# sch_station_de_charge.net
KiCad netlist of a schematic drawn in Altium Designer
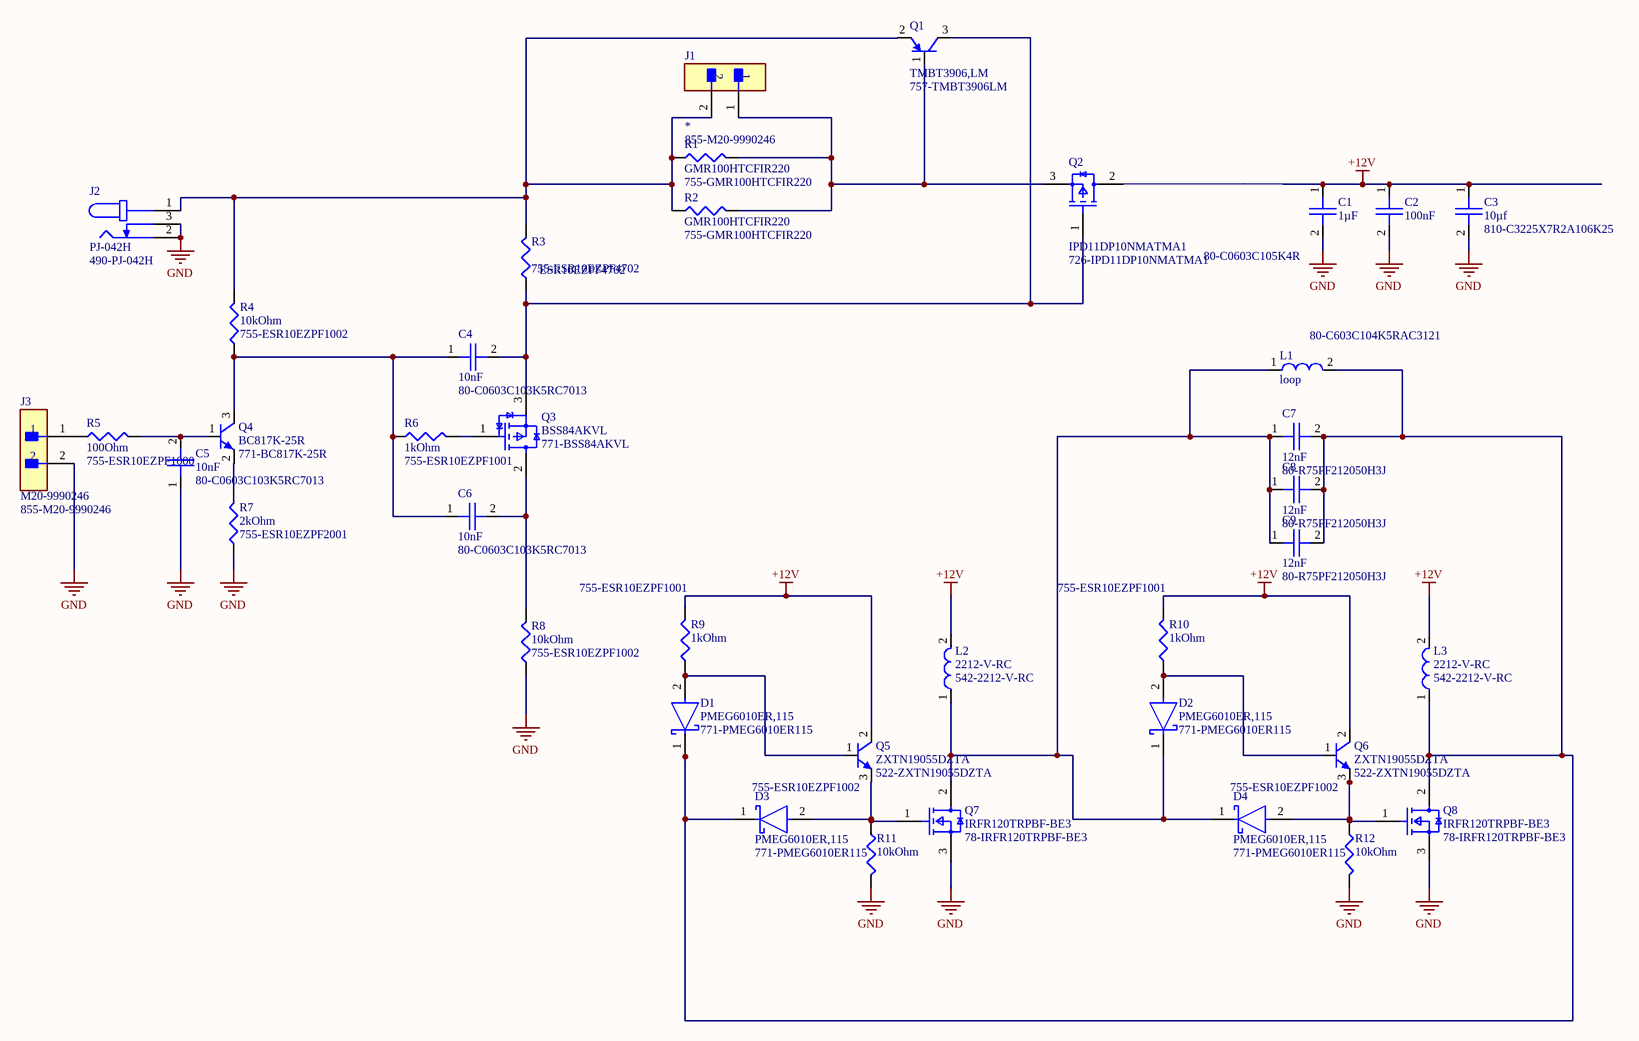
[diagram p0: sch_station_de_charge.SchDoc]

(export (version "E")
  (design (tool "Eeschema 10.0.6"))
  (components
    (comp (ref "C1")
      (value "1µF")
      (footprint "CAPC1608X90X35NL15T15")
      (description "Cap Ceramic 1uF 16V X7R 10% SMD 0603 125°C Paper T/R")
      (fields
        (field (name "MANUFACTURER") "KEMET")
        (field (name "MANUFACTURER PART NUMBER") "C0603C105K4RACTU")
        (field (name "SUPPLIER PART NUMBER 1") "80-C0603C105K4R")
      )
      (libsource (lib "station_de_charge_SchLib") (part "C0603C105K4RACTU"))
    )
    (comp (ref "C2")
      (value "100nF")
      (footprint "FP-C0603C104K5RAC3121-IPC_A")
      (description "Cap Ceramic 0.1uF 50V X7R 10% Pad SMD 0603 125°C T/R")
      (fields
        (field (name "MANUFACTURER") "KEMET")
        (field (name "MANUFACTURER PART NUMBER") "C0603C104K5RAC3121")
        (field (name "SUPPLIER PART NUMBER 1") "80-C603C104K5RAC3121")
      )
      (libsource (lib "lib_station_de_charge") (part "C0603C104K5RAC3121"))
    )
    (comp (ref "C3")
      (value "10µf")
      (footprint "CAPC3225X280N")
      (description "Multilayer Ceramic Chip Capacitors, Capacitance=10μF, LxWxT: 3.2x2.5x2.5mm")
      (fields
        (field (name "MANUFACTURER") "TDK")
        (field (name "MANUFACTURER PART NUMBER") "C3225X7R2A106K250AC")
        (field (name "SUPPLIER PART NUMBER 1") "810-C3225X7R2A106K25")
      )
      (libsource (lib "station_de_charge_SchLib") (part "C3225X7R2A106K250AC"))
    )
    (comp (ref "C4")
      (value "10nF")
      (footprint "FP-C0603C104K5RAC3121-IPC_A")
      (description "Cap Ceramic 0.01uF 50V X7R 10% Pad SMD 0603 125C T/R")
      (fields
        (field (name "MANUFACTURER") "KEMET")
        (field (name "MANUFACTURER PART NUMBER") "C0603C103K5RAC7013")
        (field (name "SUPPLIER PART NUMBER 1") "80-C0603C103K5RC7013")
      )
      (libsource (lib "station_de_charge_SchLib") (part "C0603C103K5RAC7013"))
    )
    (comp (ref "C5")
      (value "10nF")
      (footprint "FP-C0603C104K5RAC3121-IPC_A")
      (description "Cap Ceramic 0.01uF 50V X7R 10% Pad SMD 0603 125C T/R")
      (fields
        (field (name "MANUFACTURER") "KEMET")
        (field (name "MANUFACTURER PART NUMBER") "C0603C103K5RAC7013")
        (field (name "SUPPLIER PART NUMBER 1") "80-C0603C103K5RC7013")
      )
      (libsource (lib "station_de_charge_SchLib") (part "C0603C103K5RAC7013"))
    )
    (comp (ref "C6")
      (value "10nF")
      (footprint "FP-C0603C104K5RAC3121-IPC_A")
      (description "Cap Ceramic 0.01uF 50V X7R 10% Pad SMD 0603 125C T/R")
      (fields
        (field (name "MANUFACTURER") "KEMET")
        (field (name "MANUFACTURER PART NUMBER") "C0603C103K5RAC7013")
        (field (name "SUPPLIER PART NUMBER 1") "80-C0603C103K5RC7013")
      )
      (libsource (lib "station_de_charge_SchLib") (part "C0603C103K5RAC7013"))
    )
    (comp (ref "C7")
      (value "12nF")
      (footprint "R75PF212050H3J")
      (description "Cap Film 0.012uF 630V PP 5% Molded Solder Pin 10mm 125°C Bulk")
      (fields
        (field (name "MANUFACTURER") "KEMET")
        (field (name "MANUFACTURER PART NUMBER") "R75PF212050H3J")
        (field (name "SUPPLIER PART NUMBER 1") "80-R75PF212050H3J")
      )
      (libsource (lib "station_de_charge_SchLib") (part "R75PF212050H3J"))
    )
    (comp (ref "C8")
      (value "12nF")
      (footprint "R75PF212050H3J")
      (description "Cap Film 0.012uF 630V PP 5% Molded Solder Pin 10mm 125°C Bulk")
      (fields
        (field (name "MANUFACTURER") "KEMET")
        (field (name "MANUFACTURER PART NUMBER") "R75PF212050H3J")
        (field (name "SUPPLIER PART NUMBER 1") "80-R75PF212050H3J")
      )
      (libsource (lib "station_de_charge_SchLib") (part "R75PF212050H3J"))
    )
    (comp (ref "C9")
      (value "12nF")
      (footprint "R75PF212050H3J")
      (description "Cap Film 0.012uF 630V PP 5% Molded Solder Pin 10mm 125°C Bulk")
      (fields
        (field (name "MANUFACTURER") "KEMET")
        (field (name "MANUFACTURER PART NUMBER") "R75PF212050H3J")
        (field (name "SUPPLIER PART NUMBER 1") "80-R75PF212050H3J")
      )
      (libsource (lib "station_de_charge_SchLib") (part "R75PF212050H3J"))
    )
    (comp (ref "D1")
      (value "PMEG6010ER,115")
      (footprint "TVS_PTVS13VS1UR,115")
      (description "DIODE SCHOTTKY 60V 1A SOD123W")
      (fields
        (field (name "MANUFACTURER") "Nexperia")
        (field (name "SUPPLIER PART NUMBER 1") "771-PMEG6010ER115")
      )
      (libsource (lib "station_de_charge_SchLib") (part "PMEG6010ER,115"))
    )
    (comp (ref "D2")
      (value "PMEG6010ER,115")
      (footprint "TVS_PTVS13VS1UR,115")
      (description "DIODE SCHOTTKY 60V 1A SOD123W")
      (fields
        (field (name "MANUFACTURER") "Nexperia")
        (field (name "SUPPLIER PART NUMBER 1") "771-PMEG6010ER115")
      )
      (libsource (lib "station_de_charge_SchLib") (part "PMEG6010ER,115"))
    )
    (comp (ref "D3")
      (value "PMEG6010ER,115")
      (footprint "TVS_PTVS13VS1UR,115")
      (description "DIODE SCHOTTKY 60V 1A SOD123W")
      (fields
        (field (name "MANUFACTURER") "Nexperia")
        (field (name "SUPPLIER PART NUMBER 1") "771-PMEG6010ER115")
      )
      (libsource (lib "station_de_charge_SchLib") (part "PMEG6010ER,115"))
    )
    (comp (ref "D4")
      (value "PMEG6010ER,115")
      (footprint "TVS_PTVS13VS1UR,115")
      (description "DIODE SCHOTTKY 60V 1A SOD123W")
      (fields
        (field (name "MANUFACTURER") "Nexperia")
        (field (name "SUPPLIER PART NUMBER 1") "771-PMEG6010ER115")
      )
      (libsource (lib "station_de_charge_SchLib") (part "PMEG6010ER,115"))
    )
    (comp (ref "J1")
      (value "*")
      (footprint "FP-M20-9990246-MFG")
      (description "2.54mm (0.1\") Pitch SIL Vertical PC Tail Pin Header, 6.1mm mating pin height, tin, 2 contacts")
      (fields
        (field (name "MANUFACTURER") "Harwin")
        (field (name "MANUFACTURER PART NUMBER") "M20-9990246")
        (field (name "SUPPLIER PART NUMBER 1") "855-M20-9990246")
      )
      (libsource (lib "*") (part "M20-9990246"))
    )
    (comp (ref "J2")
      (value "PJ-042H")
      (footprint "CUI_PJ-042H")
      (description "1.65 x 5.15 mm, 5.0 A, Horizontal, Through Hole, Kinked Pins, Dc Power Jack Connector")
      (fields
        (field (name "MANUFACTURER") "CUI Devices")
        (field (name "SUPPLIER PART NUMBER 1") "490-PJ-042H")
      )
      (libsource (lib "station_de_charge_SchLib") (part "PJ-042H"))
    )
    (comp (ref "J3")
      (value "M20-9990246")
      (footprint "FP-M20-9990246-MFG")
      (description "2.54mm (0.1\") Pitch SIL Vertical PC Tail Pin Header, 6.1mm mating pin height, tin, 2 contacts")
      (fields
        (field (name "MANUFACTURER") "Harwin")
        (field (name "SUPPLIER PART NUMBER 1") "855-M20-9990246")
      )
      (libsource (lib "station_de_charge_SchLib") (part "M20-9990246"))
    )
    (comp (ref "L1")
      (value "loop")
      (footprint "loop")
      (libsource (lib "station_de_charge_SchLib") (part "loop"))
    )
    (comp (ref "L2")
      (value "2212-V-RC")
      (footprint "IND_HCTI-220-5.8")
      (description "Inductor High Current Toroid 100uH/64uH 15% 1KHz 4.4A 56mOhm DCR RDL")
      (fields
        (field (name "MANUFACTURER") "Bourns JW Miller")
        (field (name "TOLERANCE") "15%")
        (field (name "SUPPLIER PART NUMBER 1") "542-2212-V-RC")
      )
      (libsource (lib "station_de_charge_SchLib") (part "2212-V-RC"))
    )
    (comp (ref "L3")
      (value "2212-V-RC")
      (footprint "IND_HCTI-220-5.8")
      (description "Inductor High Current Toroid 100uH/64uH 15% 1KHz 4.4A 56mOhm DCR RDL")
      (fields
        (field (name "MANUFACTURER") "Bourns JW Miller")
        (field (name "TOLERANCE") "15%")
        (field (name "SUPPLIER PART NUMBER 1") "542-2212-V-RC")
      )
      (libsource (lib "station_de_charge_SchLib") (part "2212-V-RC"))
    )
    (comp (ref "Q1")
      (value "TMBT3906,LM")
      (footprint "FP-TMBT3906")
      (description "TRANSPNP50V0.15ASOT23-3")
      (fields
        (field (name "MANUFACTURER") "Toshiba")
        (field (name "SUPPLIER PART NUMBER 1") "757-TMBT3906LM")
      )
      (libsource (lib "station_de_charge_SchLib") (part "TMBT3906,LM"))
    )
    (comp (ref "Q2")
      (value "IPD11DP10NMATMA1")
      (footprint "FP-IPD11DP10NM")
      (description "Mosfet, P-ch, 100V, TO-252-3 Rohs Compliant: Yes")
      (fields
        (field (name "MANUFACTURER") "Infineon")
        (field (name "SUPPLIER PART NUMBER 1") "726-IPD11DP10NMATMA1")
      )
      (libsource (lib "station_de_charge_SchLib") (part "IPD11DP10NMATMA1"))
    )
    (comp (ref "Q3")
      (value "BSS84AKVL")
      (footprint "SOT95P230X110-3N")
      (description "BSS84AKV/SOT666/SOT6")
      (fields
        (field (name "MANUFACTURER") "Nexperia")
        (field (name "SUPPLIER PART NUMBER 1") "771-BSS84AKVL")
      )
      (libsource (lib "station_de_charge_SchLib") (part "BSS84AKVL"))
    )
    (comp (ref "Q4")
      (value "BC817K-25R")
      (footprint "SOT95P230X110-3N")
      (description "BC817K-25H/SOT23/TO-236AB")
      (fields
        (field (name "MANUFACTURER") "Nexperia")
        (field (name "SUPPLIER PART NUMBER 1") "771-BC817K-25R")
      )
      (libsource (lib "station_de_charge_SchLib") (part "BC817K-25R"))
    )
    (comp (ref "Q5")
      (value "ZXTN19055DZTA")
      (footprint "VREG_AP2204RA-3.3TRG1")
      (description "TRANS NPN 55V 6A SOT89")
      (fields
        (field (name "MANUFACTURER") "Diodes Zetex")
        (field (name "SUPPLIER PART NUMBER 1") "522-ZXTN19055DZTA")
      )
      (libsource (lib "lib_station_de_charge") (part "ZXTN19055DZTA"))
    )
    (comp (ref "Q6")
      (value "ZXTN19055DZTA")
      (footprint "VREG_AP2204RA-3.3TRG1")
      (description "TRANS NPN 55V 6A SOT89")
      (fields
        (field (name "MANUFACTURER") "Diodes Zetex")
        (field (name "SUPPLIER PART NUMBER 1") "522-ZXTN19055DZTA")
      )
      (libsource (lib "lib_station_de_charge") (part "ZXTN19055DZTA"))
    )
    (comp (ref "Q7")
      (value "IRFR120TRPBF-BE3")
      (footprint "FP-IRFR120TRPBF-BE3")
      (fields
        (field (name "MANUFACTURER") "Vishay Siliconix")
        (field (name "SUPPLIER PART NUMBER 1") "78-IRFR120TRPBF-BE3")
      )
      (libsource (lib "station_de_charge_SchLib") (part "IRFR120TRPBF-BE3"))
    )
    (comp (ref "Q8")
      (value "IRFR120TRPBF-BE3")
      (footprint "FP-IRFR120TRPBF-BE3")
      (fields
        (field (name "MANUFACTURER") "Vishay Siliconix")
        (field (name "SUPPLIER PART NUMBER 1") "78-IRFR120TRPBF-BE3")
      )
      (libsource (lib "station_de_charge_SchLib") (part "IRFR120TRPBF-BE3"))
    )
    (comp (ref "R1")
      (value "GMR100HTCFIR220")
      (footprint "RESC6432X55N")
      (description "Res Current Sense Metal Plate 2512 0.1 Ohm 1% 3W ±20ppm/°C Molded Emboss T/R")
      (fields
        (field (name "MANUFACTURER") "Rohm")
        (field (name "TOLERANCE") "1%")
        (field (name "SUPPLIER PART NUMBER 1") "755-GMR100HTCFIR220")
      )
      (libsource (lib "station_de_charge_SchLib") (part "GMR100HTCFIR220"))
    )
    (comp (ref "R2")
      (value "GMR100HTCFIR220")
      (footprint "RESC6432X55N")
      (description "Res Current Sense Metal Plate 2512 0.1 Ohm 1% 3W ±20ppm/°C Molded Emboss T/R")
      (fields
        (field (name "MANUFACTURER") "Rohm")
        (field (name "TOLERANCE") "1%")
        (field (name "SUPPLIER PART NUMBER 1") "755-GMR100HTCFIR220")
      )
      (libsource (lib "station_de_charge_SchLib") (part "GMR100HTCFIR220"))
    )
    (comp (ref "R3")
      (value "ESR10EZPF4702")
      (footprint "FP-ESR10-IPC_A")
      (description "Res Thick Film 0805 47K Ohm 1% 0.4W ±100ppm/C Pad SMD Automotive T/R")
      (fields
        (field (name "MANUFACTURER") "Rohm")
        (field (name "TOLERANCE") "1%")
        (field (name "SUPPLIER PART NUMBER 1") "755-ESR10EZPF4702")
      )
      (libsource (lib "station_de_charge_SchLib") (part "ESR10EZPF4702"))
    )
    (comp (ref "R4")
      (value "10kOhm")
      (footprint "FP-ESR10-IPC_A")
      (description "Res Thick Film 0805 10K Ohm 1% 0.4W ±100ppm/C Pad SMD Automotive T/R")
      (fields
        (field (name "MANUFACTURER") "Rohm")
        (field (name "MANUFACTURER PART NUMBER") "ESR10EZPF1002")
        (field (name "SUPPLIER PART NUMBER 1") "755-ESR10EZPF1002")
      )
      (libsource (lib "station_de_charge_SchLib") (part "ESR10EZPF1002"))
    )
    (comp (ref "R5")
      (value "100Ohm")
      (footprint "FP-ESR10-IPC_A")
      (description "Res Thick Film 0805 100 Ohm 1% 2/5W ±100ppm/°C Molded SMD Paper T/R")
      (fields
        (field (name "MANUFACTURER") "Rohm")
        (field (name "MANUFACTURER PART NUMBER") "ESR10EZPF1000")
        (field (name "SUPPLIER PART NUMBER 1") "755-ESR10EZPF1000")
      )
      (libsource (lib "station_de_charge_SchLib") (part "ESR10EZPF1000"))
    )
    (comp (ref "R6")
      (value "1kOhm")
      (footprint "FP-ESR10-IPC_A")
      (description "Res Thick Film 0805 1K Ohm 1% 0.4W ±100ppm/C Epoxy Resin Pad SMD Automotive T/R")
      (fields
        (field (name "MANUFACTURER") "Rohm")
        (field (name "MANUFACTURER PART NUMBER") "ESR10EZPF1001")
        (field (name "SUPPLIER PART NUMBER 1") "755-ESR10EZPF1001")
      )
      (libsource (lib "station_de_charge_SchLib") (part "ESR10EZPF1001"))
    )
    (comp (ref "R7")
      (value "2kOhm")
      (footprint "FP-ESR10-IPC_A")
      (description "Res Thick Film 0805 2K Ohm 1% 2/5W ±100ppm/°C Molded SMD Paper T/R")
      (fields
        (field (name "MANUFACTURER") "Rohm")
        (field (name "MANUFACTURER PART NUMBER") "ESR10EZPF2001")
        (field (name "SUPPLIER PART NUMBER 1") "755-ESR10EZPF2001")
      )
      (libsource (lib "station_de_charge_SchLib") (part "ESR10EZPF2001"))
    )
    (comp (ref "R8")
      (value "10kOhm")
      (footprint "FP-ESR10-IPC_A")
      (description "Res Thick Film 0805 10K Ohm 1% 0.4W ±100ppm/C Pad SMD Automotive T/R")
      (fields
        (field (name "MANUFACTURER") "Rohm")
        (field (name "MANUFACTURER PART NUMBER") "ESR10EZPF1002")
        (field (name "SUPPLIER PART NUMBER 1") "755-ESR10EZPF1002")
      )
      (libsource (lib "station_de_charge_SchLib") (part "ESR10EZPF1002"))
    )
    (comp (ref "R9")
      (value "1kOhm")
      (footprint "FP-ESR10-IPC_A")
      (description "Res Thick Film 0805 1K Ohm 1% 0.4W ±100ppm/C Epoxy Resin Pad SMD Automotive T/R")
      (fields
        (field (name "MANUFACTURER") "Rohm")
        (field (name "MANUFACTURER PART NUMBER") "ESR10EZPF1001")
        (field (name "SUPPLIER PART NUMBER 1") "755-ESR10EZPF1001")
      )
      (libsource (lib "lib_station_de_charge") (part "ESR10EZPF1001"))
    )
    (comp (ref "R10")
      (value "1kOhm")
      (footprint "FP-ESR10-IPC_A")
      (description "Res Thick Film 0805 1K Ohm 1% 0.4W ±100ppm/C Epoxy Resin Pad SMD Automotive T/R")
      (fields
        (field (name "MANUFACTURER") "Rohm")
        (field (name "MANUFACTURER PART NUMBER") "ESR10EZPF1001")
        (field (name "SUPPLIER PART NUMBER 1") "755-ESR10EZPF1001")
      )
      (libsource (lib "lib_station_de_charge") (part "ESR10EZPF1001"))
    )
    (comp (ref "R11")
      (value "10kOhm")
      (footprint "FP-ESR10-IPC_A")
      (description "Res Thick Film 0805 10K Ohm 1% 0.4W ±100ppm/C Pad SMD Automotive T/R")
      (fields
        (field (name "MANUFACTURER") "Rohm")
        (field (name "MANUFACTURER PART NUMBER") "ESR10EZPF1002")
        (field (name "SUPPLIER PART NUMBER 1") "755-ESR10EZPF1002")
      )
      (libsource (lib "lib_station_de_charge") (part "ESR10EZPF1002"))
    )
    (comp (ref "R12")
      (value "10kOhm")
      (footprint "FP-ESR10-IPC_A")
      (description "Res Thick Film 0805 10K Ohm 1% 0.4W ±100ppm/C Pad SMD Automotive T/R")
      (fields
        (field (name "MANUFACTURER") "Rohm")
        (field (name "MANUFACTURER PART NUMBER") "ESR10EZPF1002")
        (field (name "SUPPLIER PART NUMBER 1") "755-ESR10EZPF1002")
      )
      (libsource (lib "lib_station_de_charge") (part "ESR10EZPF1002"))
    )
  )
  (nets
    (net (code "1") (name "+12V") (class "Default")
      (node (ref "C1") (pin "1") (pinfunction "1_1") (pintype "passive"))
      (node (ref "C2") (pin "1") (pinfunction "1_1") (pintype "passive"))
      (node (ref "C3") (pin "1") (pinfunction "1_1") (pintype "passive"))
      (node (ref "L2") (pin "2") (pinfunction "2_2") (pintype "passive"))
      (node (ref "L3") (pin "2") (pinfunction "2_2") (pintype "passive"))
      (node (ref "Q2") (pin "2") (pinfunction "DRAIN_2") (pintype "passive"))
      (node (ref "Q5") (pin "2") (pinfunction "E_2") (pintype "passive"))
      (node (ref "Q6") (pin "2") (pinfunction "E_2") (pintype "passive"))
      (node (ref "R10") (pin "2") (pinfunction "2_2") (pintype "passive"))
      (node (ref "R9") (pin "2") (pinfunction "2_2") (pintype "passive"))
    )
    (net (code "2") (name "GND") (class "Default")
      (node (ref "C1") (pin "2") (pinfunction "2_2") (pintype "passive"))
      (node (ref "C2") (pin "2") (pinfunction "2_2") (pintype "passive"))
      (node (ref "C3") (pin "2") (pinfunction "2_2") (pintype "passive"))
      (node (ref "C5") (pin "1") (pinfunction "1_1") (pintype "passive"))
      (node (ref "J2") (pin "2") (pinfunction "2_2") (pintype "passive"))
      (node (ref "J2") (pin "3") (pinfunction "3_3") (pintype "passive"))
      (node (ref "J3") (pin "2") (pinfunction "2_2") (pintype "passive"))
      (node (ref "Q7") (pin "3") (pinfunction "SOURCE_3") (pintype "passive"))
      (node (ref "Q8") (pin "3") (pinfunction "SOURCE_3") (pintype "passive"))
      (node (ref "R11") (pin "2") (pinfunction "2_2") (pintype "passive"))
      (node (ref "R12") (pin "2") (pinfunction "2_2") (pintype "passive"))
      (node (ref "R7") (pin "1") (pinfunction "1_1") (pintype "passive"))
      (node (ref "R8") (pin "1") (pinfunction "1_1") (pintype "passive"))
    )
    (net (code "3") (name "Net-(D1-A)") (class "Default")
      (node (ref "D1") (pin "2") (pinfunction "A_2") (pintype "passive"))
      (node (ref "Q5") (pin "1") (pinfunction "B_1") (pintype "passive"))
      (node (ref "R9") (pin "1") (pinfunction "1_1") (pintype "passive"))
    )
    (net (code "4") (name "Net-(D1-C)") (class "Default")
      (node (ref "C7") (pin "2") (pinfunction "2_2") (pintype "passive"))
      (node (ref "C8") (pin "2") (pinfunction "2_2") (pintype "passive"))
      (node (ref "C9") (pin "2") (pinfunction "2_2") (pintype "passive"))
      (node (ref "D1") (pin "1") (pinfunction "C_1") (pintype "passive"))
      (node (ref "D3") (pin "1") (pinfunction "C_1") (pintype "passive"))
      (node (ref "L1") (pin "2") (pinfunction "2_2") (pintype "passive"))
      (node (ref "L3") (pin "1") (pinfunction "1_1") (pintype "passive"))
      (node (ref "Q8") (pin "2") (pinfunction "DRAIN_2") (pintype "passive"))
    )
    (net (code "5") (name "Net-(D2-A)") (class "Default")
      (node (ref "D2") (pin "2") (pinfunction "A_2") (pintype "passive"))
      (node (ref "Q6") (pin "1") (pinfunction "B_1") (pintype "passive"))
      (node (ref "R10") (pin "1") (pinfunction "1_1") (pintype "passive"))
    )
    (net (code "6") (name "Net-(D2-C)") (class "Default")
      (node (ref "C7") (pin "1") (pinfunction "1_1") (pintype "passive"))
      (node (ref "C8") (pin "1") (pinfunction "1_1") (pintype "passive"))
      (node (ref "C9") (pin "1") (pinfunction "1_1") (pintype "passive"))
      (node (ref "D2") (pin "1") (pinfunction "C_1") (pintype "passive"))
      (node (ref "D4") (pin "1") (pinfunction "C_1") (pintype "passive"))
      (node (ref "L1") (pin "1") (pinfunction "1_1") (pintype "passive"))
      (node (ref "L2") (pin "1") (pinfunction "1_1") (pintype "passive"))
      (node (ref "Q7") (pin "2") (pinfunction "DRAIN_2") (pintype "passive"))
    )
    (net (code "7") (name "Net-(D3-A)") (class "Default")
      (node (ref "D3") (pin "2") (pinfunction "A_2") (pintype "passive"))
      (node (ref "Q5") (pin "3") (pinfunction "C_3") (pintype "passive"))
      (node (ref "Q7") (pin "1") (pinfunction "GATE_1") (pintype "passive"))
      (node (ref "R11") (pin "1") (pinfunction "1_1") (pintype "passive"))
    )
    (net (code "8") (name "Net-(D4-A)") (class "Default")
      (node (ref "D4") (pin "2") (pinfunction "A_2") (pintype "passive"))
      (node (ref "Q6") (pin "3") (pinfunction "C_3") (pintype "passive"))
      (node (ref "Q8") (pin "1") (pinfunction "GATE_1") (pintype "passive"))
      (node (ref "R12") (pin "1") (pinfunction "1_1") (pintype "passive"))
    )
    (net (code "9") (name "Net-(J3-Pad1)") (class "Default")
      (node (ref "J3") (pin "1") (pinfunction "1_1") (pintype "passive"))
      (node (ref "R5") (pin "1") (pinfunction "1_1") (pintype "passive"))
    )
    (net (code "10") (name "Net-(Q1-B)") (class "Default")
      (node (ref "J1") (pin "1") (pinfunction "1_1") (pintype "passive"))
      (node (ref "Q1") (pin "1") (pinfunction "B_1") (pintype "passive"))
      (node (ref "Q2") (pin "3") (pinfunction "SOURCE_3") (pintype "passive"))
      (node (ref "R1") (pin "2") (pinfunction "2_2") (pintype "passive"))
      (node (ref "R2") (pin "2") (pinfunction "2_2") (pintype "passive"))
    )
    (net (code "11") (name "Net-(Q1-C)") (class "Default")
      (node (ref "C4") (pin "2") (pinfunction "2_2") (pintype "passive"))
      (node (ref "Q1") (pin "3") (pinfunction "C_3") (pintype "passive"))
      (node (ref "Q2") (pin "1") (pinfunction "GATE_1") (pintype "passive"))
      (node (ref "Q3") (pin "3") (pinfunction "SOURCE_3") (pintype "passive"))
      (node (ref "R3") (pin "1") (pinfunction "1_1") (pintype "passive"))
    )
    (net (code "12") (name "Net-(Q1-E)") (class "Default")
      (node (ref "J1") (pin "2") (pinfunction "2_2") (pintype "passive"))
      (node (ref "J2") (pin "1") (pinfunction "1_1") (pintype "passive"))
      (node (ref "Q1") (pin "2") (pinfunction "E_2") (pintype "passive"))
      (node (ref "R1") (pin "1") (pinfunction "1_1") (pintype "passive"))
      (node (ref "R2") (pin "1") (pinfunction "1_1") (pintype "passive"))
      (node (ref "R3") (pin "2") (pinfunction "2_2") (pintype "passive"))
      (node (ref "R4") (pin "2") (pinfunction "2_2") (pintype "passive"))
    )
    (net (code "13") (name "Net-(Q3-DRAIN)") (class "Default")
      (node (ref "C6") (pin "2") (pinfunction "2_2") (pintype "passive"))
      (node (ref "Q3") (pin "2") (pinfunction "DRAIN_2") (pintype "passive"))
      (node (ref "R8") (pin "2") (pinfunction "2_2") (pintype "passive"))
    )
    (net (code "14") (name "Net-(Q3-GATE)") (class "Default")
      (node (ref "Q3") (pin "1") (pinfunction "GATE_1") (pintype "passive"))
      (node (ref "R6") (pin "2") (pinfunction "2_2") (pintype "passive"))
    )
    (net (code "15") (name "Net-(Q4-B)") (class "Default")
      (node (ref "C5") (pin "2") (pinfunction "2_2") (pintype "passive"))
      (node (ref "Q4") (pin "1") (pinfunction "B_1") (pintype "passive"))
      (node (ref "R5") (pin "2") (pinfunction "2_2") (pintype "passive"))
    )
    (net (code "16") (name "Net-(Q4-C)") (class "Default")
      (node (ref "C4") (pin "1") (pinfunction "1_1") (pintype "passive"))
      (node (ref "C6") (pin "1") (pinfunction "1_1") (pintype "passive"))
      (node (ref "Q4") (pin "3") (pinfunction "C_3") (pintype "passive"))
      (node (ref "R4") (pin "1") (pinfunction "1_1") (pintype "passive"))
      (node (ref "R6") (pin "1") (pinfunction "1_1") (pintype "passive"))
    )
    (net (code "17") (name "Net-(Q4-E)") (class "Default")
      (node (ref "Q4") (pin "2") (pinfunction "E_2") (pintype "passive"))
      (node (ref "R7") (pin "2") (pinfunction "2_2") (pintype "passive"))
    )
  )
)
